# attiny24.net
KiCad netlist of a schematic drawn in EAGLE
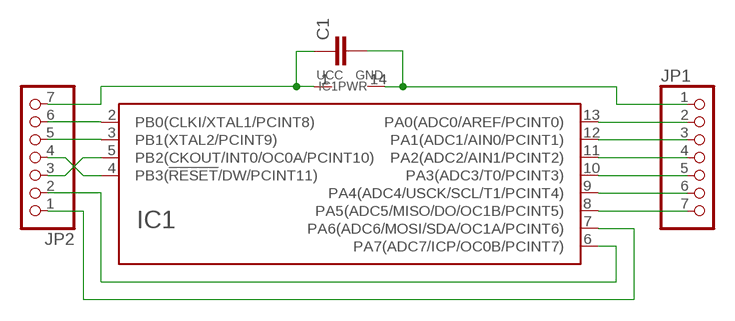
[diagram p0: schematic, sheet 1]

(export (version "E")
  (design (tool "Eeschema 10.0.6"))
  (components
    (comp (ref "C1")
      (value "C-EUC0805K")
      (footprint "eagle-import:C0805K")
      (libsource (lib "eagle-import") (part "C-EUC0805K"))
    )
    (comp (ref "IC1")
      (value "ATTINY24/44/84-SSU")
      (footprint "eagle-import:SOIC14")
      (libsource (lib "eagle-import") (part "ATTINY24/44/84-SSU"))
    )
    (comp (ref "JP1")
      (value "PINHD-1X7")
      (footprint "eagle-import:1X07")
      (libsource (lib "eagle-import") (part "PINHD-1X7"))
    )
    (comp (ref "JP2")
      (value "PINHD-1X7")
      (footprint "eagle-import:1X07")
      (libsource (lib "eagle-import") (part "PINHD-1X7"))
    )
  )
  (nets
    (net (code "1") (name "Net-(IC1A-PA0(ADC0{slash}AREF{slash}PCINT0))") (class "Default")
      (node (ref "IC1") (pin "13") (pinfunction "PA0(ADC0/AREF/PCINT0)_13") (pintype "bidirectional"))
      (node (ref "JP1") (pin "2") (pinfunction "2_2") (pintype "passive"))
    )
    (net (code "2") (name "Net-(IC1A-PA1(ADC1{slash}AIN0{slash}PCINT1))") (class "Default")
      (node (ref "IC1") (pin "12") (pinfunction "PA1(ADC1/AIN0/PCINT1)_12") (pintype "bidirectional"))
      (node (ref "JP1") (pin "3") (pinfunction "3_3") (pintype "passive"))
    )
    (net (code "3") (name "Net-(IC1A-PA2(ADC2{slash}AIN1{slash}PCINT2))") (class "Default")
      (node (ref "IC1") (pin "11") (pinfunction "PA2(ADC2/AIN1/PCINT2)_11") (pintype "bidirectional"))
      (node (ref "JP1") (pin "4") (pinfunction "4_4") (pintype "passive"))
    )
    (net (code "4") (name "Net-(IC1A-PA3(ADC3{slash}T0{slash}PCINT3))") (class "Default")
      (node (ref "IC1") (pin "10") (pinfunction "PA3(ADC3/T0/PCINT3)_10") (pintype "bidirectional"))
      (node (ref "JP1") (pin "5") (pinfunction "5_5") (pintype "passive"))
    )
    (net (code "5") (name "Net-(IC1A-PA4(ADC4{slash}USCK{slash}SCL{slash}T1{slash}PCINT4))") (class "Default")
      (node (ref "IC1") (pin "9") (pinfunction "PA4(ADC4/USCK/SCL/T1/PCINT4)_9") (pintype "bidirectional"))
      (node (ref "JP1") (pin "6") (pinfunction "6_6") (pintype "passive"))
    )
    (net (code "6") (name "Net-(IC1A-PA5(ADC5{slash}MISO{slash}DO{slash}OC1B{slash}PCINT5))") (class "Default")
      (node (ref "IC1") (pin "8") (pinfunction "PA5(ADC5/MISO/DO/OC1B/PCINT5)_8") (pintype "bidirectional"))
      (node (ref "JP1") (pin "7") (pinfunction "7_7") (pintype "passive"))
    )
    (net (code "7") (name "Net-(IC1A-PA6(ADC6{slash}MOSI{slash}SDA{slash}OC1A{slash}PCINT6))") (class "Default")
      (node (ref "IC1") (pin "7") (pinfunction "PA6(ADC6/MOSI/SDA/OC1A/PCINT6)_7") (pintype "bidirectional"))
      (node (ref "JP2") (pin "1") (pinfunction "1_1") (pintype "passive"))
    )
    (net (code "8") (name "Net-(IC1A-PA7(ADC7{slash}ICP{slash}OC0B{slash}PCINT7))") (class "Default")
      (node (ref "IC1") (pin "6") (pinfunction "PA7(ADC7/ICP/OC0B/PCINT7)_6") (pintype "bidirectional"))
      (node (ref "JP2") (pin "2") (pinfunction "2_2") (pintype "passive"))
    )
    (net (code "9") (name "Net-(IC1A-PB0(CLKI{slash}XTAL1{slash}PCINT8))") (class "Default")
      (node (ref "IC1") (pin "2") (pinfunction "PB0(CLKI/XTAL1/PCINT8)_2") (pintype "bidirectional"))
      (node (ref "JP2") (pin "6") (pinfunction "6_6") (pintype "passive"))
    )
    (net (code "10") (name "Net-(IC1A-PB1(XTAL2{slash}PCINT9))") (class "Default")
      (node (ref "IC1") (pin "3") (pinfunction "PB1(XTAL2/PCINT9)_3") (pintype "bidirectional"))
      (node (ref "JP2") (pin "5") (pinfunction "5_5") (pintype "passive"))
    )
    (net (code "11") (name "Net-(IC1A-PB2(CKOUT{slash}INT0{slash}OC0A{slash}PCINT10))") (class "Default")
      (node (ref "IC1") (pin "5") (pinfunction "PB2(CKOUT/INT0/OC0A/PCINT10)_5") (pintype "bidirectional"))
      (node (ref "JP2") (pin "3") (pinfunction "3_3") (pintype "passive"))
    )
    (net (code "12") (name "Net-(IC1A-PB3(~{RESET}{slash}DW{slash}PCINT11))") (class "Default")
      (node (ref "IC1") (pin "4") (pinfunction "PB3(~{RESET}/DW/PCINT11)_4") (pintype "bidirectional"))
      (node (ref "JP2") (pin "4") (pinfunction "4_4") (pintype "passive"))
    )
    (net (code "13") (name "Net-(IC1B-GND)") (class "Default")
      (node (ref "C1") (pin "2") (pinfunction "2_2") (pintype "passive"))
      (node (ref "IC1") (pin "14") (pinfunction "GND_14") (pintype "power_in"))
      (node (ref "JP1") (pin "1") (pinfunction "1_1") (pintype "passive"))
    )
    (net (code "14") (name "Net-(IC1B-UCC)") (class "Default")
      (node (ref "C1") (pin "1") (pinfunction "1_1") (pintype "passive"))
      (node (ref "IC1") (pin "1") (pinfunction "UCC_1") (pintype "power_in"))
      (node (ref "JP2") (pin "7") (pinfunction "7_7") (pintype "passive"))
    )
  )
)
